# RS485_Port.net
KiCad netlist of a schematic drawn in Altium Designer
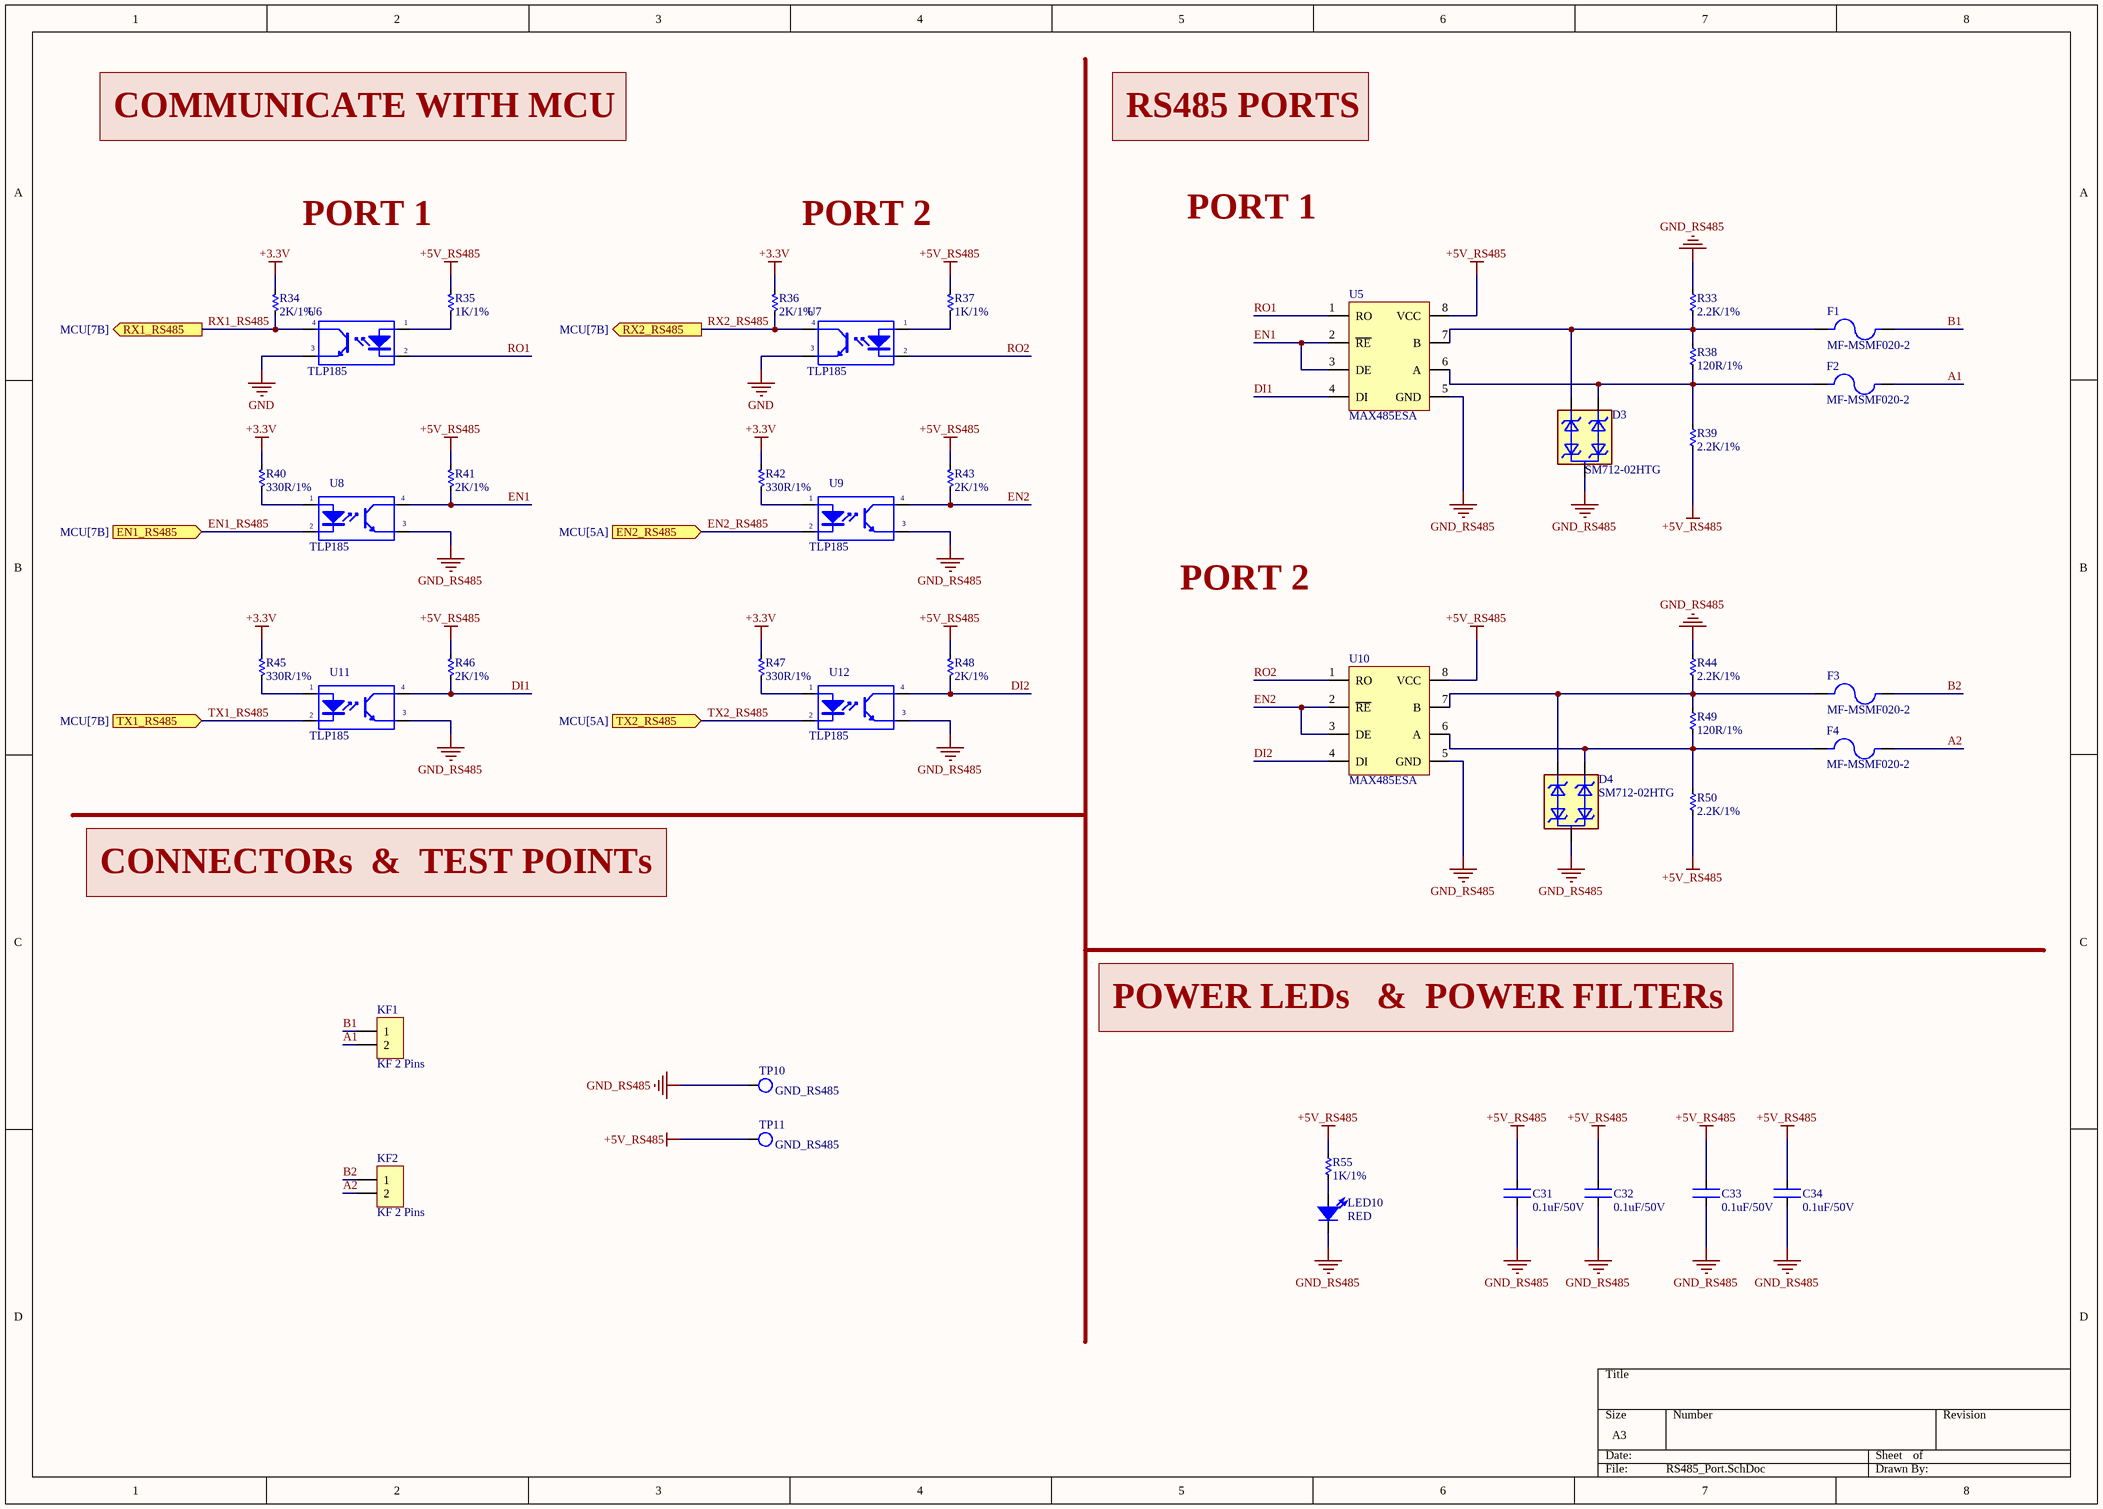
[diagram p0: RS485_Port.SchDoc]

(export (version "E")
  (design (tool "Eeschema 10.0.6"))
  (components
    (comp (ref "C31")
      (value "0.1uF/50V")
      (footprint "CAP - 0603")
      (description "CAPACITOR SMD - KEMET")
      (libsource (lib "NewLibrary") (part "CAPACITOR"))
    )
    (comp (ref "C32")
      (value "0.1uF/50V")
      (footprint "CAP - 0603")
      (description "CAPACITOR SMD - KEMET")
      (libsource (lib "NewLibrary") (part "CAPACITOR"))
    )
    (comp (ref "C33")
      (value "0.1uF/50V")
      (footprint "CAP - 0603")
      (description "CAPACITOR SMD - KEMET")
      (libsource (lib "NewLibrary") (part "CAPACITOR"))
    )
    (comp (ref "C34")
      (value "0.1uF/50V")
      (footprint "CAP - 0603")
      (description "CAPACITOR SMD - KEMET")
      (libsource (lib "NewLibrary") (part "CAPACITOR"))
    )
    (comp (ref "D3")
      (value "SM712-02HTG")
      (footprint "SOT23-3")
      (libsource (lib "NewLibrary") (part "SM712-02HTG"))
    )
    (comp (ref "D4")
      (value "SM712-02HTG")
      (footprint "SOT23-3")
      (libsource (lib "NewLibrary") (part "SM712-02HTG"))
    )
    (comp (ref "F1")
      (value "MF-MSMF020-2")
      (footprint "Fuse 4.55x3.24 mm")
      (description "Fuse Resettable 30V/0.2A; Size 4.55 x 3.24mm")
      (libsource (lib "NewLibrary") (part "MF-MSMF020-2"))
    )
    (comp (ref "F2")
      (value "MF-MSMF020-2")
      (footprint "Fuse 4.55x3.24 mm")
      (description "Fuse Resettable 30V/0.2A; Size 4.55 x 3.24mm")
      (libsource (lib "NewLibrary") (part "MF-MSMF020-2"))
    )
    (comp (ref "F3")
      (value "MF-MSMF020-2")
      (footprint "Fuse 4.55x3.24 mm")
      (description "Fuse Resettable 30V/0.2A; Size 4.55 x 3.24mm")
      (libsource (lib "NewLibrary") (part "MF-MSMF020-2"))
    )
    (comp (ref "F4")
      (value "MF-MSMF020-2")
      (footprint "Fuse 4.55x3.24 mm")
      (description "Fuse Resettable 30V/0.2A; Size 4.55 x 3.24mm")
      (libsource (lib "NewLibrary") (part "MF-MSMF020-2"))
    )
    (comp (ref "KF1")
      (value "KF 2 Pins")
      (footprint "KF-5.08-2-R")
      (description "KF Terminal Block Plug-in")
      (libsource (lib "NewLibrary") (part "KF 2 Pins"))
    )
    (comp (ref "KF2")
      (value "KF 2 Pins")
      (footprint "KF-5.08-2-R")
      (description "KF Terminal Block Plug-in")
      (libsource (lib "NewLibrary") (part "KF 2 Pins"))
    )
    (comp (ref "LED10")
      (value "RED")
      (footprint "RED_LED_0603")
      (description "LED SMD")
      (libsource (lib "NewLibrary") (part "LED_SMD"))
    )
    (comp (ref "R33")
      (value "2.2K/1%")
      (footprint "RES - 0603")
      (description "Resistor SMD - YAGEO")
      (libsource (lib "NewLibrary") (part "RESISTOR"))
    )
    (comp (ref "R34")
      (value "2K/1%")
      (footprint "RES - 0603")
      (description "Resistor SMD - YAGEO")
      (libsource (lib "NewLibrary") (part "RESISTOR"))
    )
    (comp (ref "R35")
      (value "1K/1%")
      (footprint "RES - 0603")
      (description "Resistor SMD - YAGEO")
      (libsource (lib "NewLibrary") (part "RESISTOR"))
    )
    (comp (ref "R36")
      (value "2K/1%")
      (footprint "RES - 0603")
      (description "Resistor SMD - YAGEO")
      (libsource (lib "NewLibrary") (part "RESISTOR"))
    )
    (comp (ref "R37")
      (value "1K/1%")
      (footprint "RES - 0603")
      (description "Resistor SMD - YAGEO")
      (libsource (lib "NewLibrary") (part "RESISTOR"))
    )
    (comp (ref "R38")
      (value "120R/1%")
      (footprint "RES - 0603")
      (description "Resistor SMD - YAGEO")
      (libsource (lib "NewLibrary") (part "RESISTOR"))
    )
    (comp (ref "R39")
      (value "2.2K/1%")
      (footprint "RES - 0603")
      (description "Resistor SMD - YAGEO")
      (libsource (lib "NewLibrary") (part "RESISTOR"))
    )
    (comp (ref "R40")
      (value "330R/1%")
      (footprint "RES - 0603")
      (description "Resistor SMD - YAGEO")
      (libsource (lib "NewLibrary") (part "RESISTOR"))
    )
    (comp (ref "R41")
      (value "2K/1%")
      (footprint "RES - 0603")
      (description "Resistor SMD - YAGEO")
      (libsource (lib "NewLibrary") (part "RESISTOR"))
    )
    (comp (ref "R42")
      (value "330R/1%")
      (footprint "RES - 0603")
      (description "Resistor SMD - YAGEO")
      (libsource (lib "NewLibrary") (part "RESISTOR"))
    )
    (comp (ref "R43")
      (value "2K/1%")
      (footprint "RES - 0603")
      (description "Resistor SMD - YAGEO")
      (libsource (lib "NewLibrary") (part "RESISTOR"))
    )
    (comp (ref "R44")
      (value "2.2K/1%")
      (footprint "RES - 0603")
      (description "Resistor SMD - YAGEO")
      (libsource (lib "NewLibrary") (part "RESISTOR"))
    )
    (comp (ref "R45")
      (value "330R/1%")
      (footprint "RES - 0603")
      (description "Resistor SMD - YAGEO")
      (libsource (lib "NewLibrary") (part "RESISTOR"))
    )
    (comp (ref "R46")
      (value "2K/1%")
      (footprint "RES - 0603")
      (description "Resistor SMD - YAGEO")
      (libsource (lib "NewLibrary") (part "RESISTOR"))
    )
    (comp (ref "R47")
      (value "330R/1%")
      (footprint "RES - 0603")
      (description "Resistor SMD - YAGEO")
      (libsource (lib "NewLibrary") (part "RESISTOR"))
    )
    (comp (ref "R48")
      (value "2K/1%")
      (footprint "RES - 0603")
      (description "Resistor SMD - YAGEO")
      (libsource (lib "NewLibrary") (part "RESISTOR"))
    )
    (comp (ref "R49")
      (value "120R/1%")
      (footprint "RES - 0603")
      (description "Resistor SMD - YAGEO")
      (libsource (lib "NewLibrary") (part "RESISTOR"))
    )
    (comp (ref "R50")
      (value "2.2K/1%")
      (footprint "RES - 0603")
      (description "Resistor SMD - YAGEO")
      (libsource (lib "NewLibrary") (part "RESISTOR"))
    )
    (comp (ref "R55")
      (value "1K/1%")
      (footprint "RES - 0603")
      (description "Resistor SMD - YAGEO")
      (libsource (lib "NewLibrary") (part "RESISTOR"))
    )
    (comp (ref "TP10")
      (value "GND_RS485")
      (footprint "Test Point")
      (description "Test Point")
      (libsource (lib "NewLibrary") (part "TEST POINT"))
    )
    (comp (ref "TP11")
      (value "GND_RS485")
      (footprint "Test Point")
      (description "Test Point")
      (libsource (lib "NewLibrary") (part "TEST POINT"))
    )
    (comp (ref "U5")
      (value "MAX485ESA")
      (footprint "SOP_8")
      (description "1/1 Transceiver Half RS422, RS485")
      (libsource (lib "NewLibrary") (part "MAX485ESA"))
    )
    (comp (ref "U6")
      (value "TLP185")
      (footprint "SOP-4")
      (description "TLP185 Optoisolator Transistor Output 3750Vrms 1 Channel 4-SOP")
      (libsource (lib "NewLibrary") (part "TLP185"))
    )
    (comp (ref "U7")
      (value "TLP185")
      (footprint "SOP-4")
      (description "TLP185 Optoisolator Transistor Output 3750Vrms 1 Channel 4-SOP")
      (libsource (lib "NewLibrary") (part "TLP185"))
    )
    (comp (ref "U8")
      (value "TLP185")
      (footprint "SOP-4")
      (description "TLP185 Optoisolator Transistor Output 3750Vrms 1 Channel 4-SOP")
      (libsource (lib "NewLibrary") (part "TLP185"))
    )
    (comp (ref "U9")
      (value "TLP185")
      (footprint "SOP-4")
      (description "TLP185 Optoisolator Transistor Output 3750Vrms 1 Channel 4-SOP")
      (libsource (lib "NewLibrary") (part "TLP185"))
    )
    (comp (ref "U10")
      (value "MAX485ESA")
      (footprint "SOP_8")
      (description "1/1 Transceiver Half RS422, RS485")
      (libsource (lib "NewLibrary") (part "MAX485ESA"))
    )
    (comp (ref "U11")
      (value "TLP185")
      (footprint "SOP-4")
      (description "TLP185 Optoisolator Transistor Output 3750Vrms 1 Channel 4-SOP")
      (libsource (lib "NewLibrary") (part "TLP185"))
    )
    (comp (ref "U12")
      (value "TLP185")
      (footprint "SOP-4")
      (description "TLP185 Optoisolator Transistor Output 3750Vrms 1 Channel 4-SOP")
      (libsource (lib "NewLibrary") (part "TLP185"))
    )
  )
  (nets
    (net (code "1") (name "+3.3V") (class "Default")
      (node (ref "R34") (pin "2") (pinfunction "2_2") (pintype "passive"))
      (node (ref "R36") (pin "2") (pinfunction "2_2") (pintype "passive"))
      (node (ref "R40") (pin "2") (pinfunction "2_2") (pintype "passive"))
      (node (ref "R42") (pin "2") (pinfunction "2_2") (pintype "passive"))
      (node (ref "R45") (pin "2") (pinfunction "2_2") (pintype "passive"))
      (node (ref "R47") (pin "2") (pinfunction "2_2") (pintype "passive"))
    )
    (net (code "2") (name "+5V_RS485") (class "Default")
      (node (ref "C31") (pin "1") (pinfunction "1_1") (pintype "passive"))
      (node (ref "C32") (pin "1") (pinfunction "1_1") (pintype "passive"))
      (node (ref "C33") (pin "1") (pinfunction "1_1") (pintype "passive"))
      (node (ref "C34") (pin "1") (pinfunction "1_1") (pintype "passive"))
      (node (ref "R35") (pin "2") (pinfunction "2_2") (pintype "passive"))
      (node (ref "R37") (pin "2") (pinfunction "2_2") (pintype "passive"))
      (node (ref "R39") (pin "1") (pinfunction "1_1") (pintype "passive"))
      (node (ref "R41") (pin "2") (pinfunction "2_2") (pintype "passive"))
      (node (ref "R43") (pin "2") (pinfunction "2_2") (pintype "passive"))
      (node (ref "R46") (pin "2") (pinfunction "2_2") (pintype "passive"))
      (node (ref "R48") (pin "2") (pinfunction "2_2") (pintype "passive"))
      (node (ref "R50") (pin "1") (pinfunction "1_1") (pintype "passive"))
      (node (ref "R55") (pin "1") (pinfunction "1_1") (pintype "passive"))
      (node (ref "TP11") (pin "1") (pinfunction "1_1") (pintype "passive"))
      (node (ref "U10") (pin "8") (pinfunction "VCC_8") (pintype "passive"))
      (node (ref "U5") (pin "8") (pinfunction "VCC_8") (pintype "passive"))
    )
    (net (code "3") (name "/A1") (class "Default")
      (node (ref "F2") (pin "2") (pinfunction "2_2") (pintype "passive"))
      (node (ref "KF1") (pin "2") (pinfunction "2_2") (pintype "passive"))
    )
    (net (code "4") (name "/A2") (class "Default")
      (node (ref "F4") (pin "2") (pinfunction "2_2") (pintype "passive"))
      (node (ref "KF2") (pin "2") (pinfunction "2_2") (pintype "passive"))
    )
    (net (code "5") (name "/B1") (class "Default")
      (node (ref "F1") (pin "2") (pinfunction "2_2") (pintype "passive"))
      (node (ref "KF1") (pin "1") (pinfunction "1_1") (pintype "passive"))
    )
    (net (code "6") (name "/B2") (class "Default")
      (node (ref "F3") (pin "2") (pinfunction "2_2") (pintype "passive"))
      (node (ref "KF2") (pin "1") (pinfunction "1_1") (pintype "passive"))
    )
    (net (code "7") (name "/DI1") (class "Default")
      (node (ref "R46") (pin "1") (pinfunction "1_1") (pintype "passive"))
      (node (ref "U11") (pin "4") (pinfunction "C_4") (pintype "passive"))
      (node (ref "U5") (pin "4") (pinfunction "DI_4") (pintype "passive"))
    )
    (net (code "8") (name "/DI2") (class "Default")
      (node (ref "R48") (pin "1") (pinfunction "1_1") (pintype "passive"))
      (node (ref "U10") (pin "4") (pinfunction "DI_4") (pintype "passive"))
      (node (ref "U12") (pin "4") (pinfunction "C_4") (pintype "passive"))
    )
    (net (code "9") (name "/EN1") (class "Default")
      (node (ref "R41") (pin "1") (pinfunction "1_1") (pintype "passive"))
      (node (ref "U5") (pin "2") (pinfunction "~{RE}_2") (pintype "passive"))
      (node (ref "U5") (pin "3") (pinfunction "DE_3") (pintype "passive"))
      (node (ref "U8") (pin "4") (pinfunction "C_4") (pintype "passive"))
    )
    (net (code "10") (name "/EN1_RS485") (class "Default")
      (node (ref "U8") (pin "2") (pinfunction "K_2") (pintype "passive"))
    )
    (net (code "11") (name "/EN2") (class "Default")
      (node (ref "R43") (pin "1") (pinfunction "1_1") (pintype "passive"))
      (node (ref "U10") (pin "2") (pinfunction "~{RE}_2") (pintype "passive"))
      (node (ref "U10") (pin "3") (pinfunction "DE_3") (pintype "passive"))
      (node (ref "U9") (pin "4") (pinfunction "C_4") (pintype "passive"))
    )
    (net (code "12") (name "/EN2_RS485") (class "Default")
      (node (ref "U9") (pin "2") (pinfunction "K_2") (pintype "passive"))
    )
    (net (code "13") (name "/RO1") (class "Default")
      (node (ref "U5") (pin "1") (pinfunction "RO_1") (pintype "passive"))
      (node (ref "U6") (pin "2") (pinfunction "K_2") (pintype "passive"))
    )
    (net (code "14") (name "/RO2") (class "Default")
      (node (ref "U10") (pin "1") (pinfunction "RO_1") (pintype "passive"))
      (node (ref "U7") (pin "2") (pinfunction "K_2") (pintype "passive"))
    )
    (net (code "15") (name "/RX1_RS485") (class "Default")
      (node (ref "R34") (pin "1") (pinfunction "1_1") (pintype "passive"))
      (node (ref "U6") (pin "4") (pinfunction "C_4") (pintype "passive"))
    )
    (net (code "16") (name "/RX2_RS485") (class "Default")
      (node (ref "R36") (pin "1") (pinfunction "1_1") (pintype "passive"))
      (node (ref "U7") (pin "4") (pinfunction "C_4") (pintype "passive"))
    )
    (net (code "17") (name "/TX1_RS485") (class "Default")
      (node (ref "U11") (pin "2") (pinfunction "K_2") (pintype "passive"))
    )
    (net (code "18") (name "/TX2_RS485") (class "Default")
      (node (ref "U12") (pin "2") (pinfunction "K_2") (pintype "passive"))
    )
    (net (code "19") (name "GND") (class "Default")
      (node (ref "U6") (pin "3") (pinfunction "E_3") (pintype "passive"))
      (node (ref "U7") (pin "3") (pinfunction "E_3") (pintype "passive"))
    )
    (net (code "20") (name "GND_RS485") (class "Default")
      (node (ref "C31") (pin "2") (pinfunction "2_2") (pintype "passive"))
      (node (ref "C32") (pin "2") (pinfunction "2_2") (pintype "passive"))
      (node (ref "C33") (pin "2") (pinfunction "2_2") (pintype "passive"))
      (node (ref "C34") (pin "2") (pinfunction "2_2") (pintype "passive"))
      (node (ref "D3") (pin "3") (pinfunction "3_3") (pintype "passive"))
      (node (ref "D4") (pin "3") (pinfunction "3_3") (pintype "passive"))
      (node (ref "LED10") (pin "2") (pinfunction "2_2") (pintype "passive"))
      (node (ref "R33") (pin "2") (pinfunction "2_2") (pintype "passive"))
      (node (ref "R44") (pin "2") (pinfunction "2_2") (pintype "passive"))
      (node (ref "TP10") (pin "1") (pinfunction "1_1") (pintype "passive"))
      (node (ref "U10") (pin "5") (pinfunction "GND_5") (pintype "passive"))
      (node (ref "U11") (pin "3") (pinfunction "E_3") (pintype "passive"))
      (node (ref "U12") (pin "3") (pinfunction "E_3") (pintype "passive"))
      (node (ref "U5") (pin "5") (pinfunction "GND_5") (pintype "passive"))
      (node (ref "U8") (pin "3") (pinfunction "E_3") (pintype "passive"))
      (node (ref "U9") (pin "3") (pinfunction "E_3") (pintype "passive"))
    )
    (net (code "21") (name "Net-(LED10-Pad1)") (class "Default")
      (node (ref "LED10") (pin "1") (pinfunction "1_1") (pintype "passive"))
      (node (ref "R55") (pin "2") (pinfunction "2_2") (pintype "passive"))
    )
    (net (code "22") (name "Net-(U5-A)") (class "Default")
      (node (ref "D3") (pin "1") (pinfunction "1_1") (pintype "passive"))
      (node (ref "F2") (pin "1") (pinfunction "1_1") (pintype "passive"))
      (node (ref "R38") (pin "1") (pinfunction "1_1") (pintype "passive"))
      (node (ref "R39") (pin "2") (pinfunction "2_2") (pintype "passive"))
      (node (ref "U5") (pin "6") (pinfunction "A_6") (pintype "passive"))
    )
    (net (code "23") (name "Net-(U5-B)") (class "Default")
      (node (ref "D3") (pin "2") (pinfunction "2_2") (pintype "passive"))
      (node (ref "F1") (pin "1") (pinfunction "1_1") (pintype "passive"))
      (node (ref "R33") (pin "1") (pinfunction "1_1") (pintype "passive"))
      (node (ref "R38") (pin "2") (pinfunction "2_2") (pintype "passive"))
      (node (ref "U5") (pin "7") (pinfunction "B_7") (pintype "passive"))
    )
    (net (code "24") (name "Net-(U6-A)") (class "Default")
      (node (ref "R35") (pin "1") (pinfunction "1_1") (pintype "passive"))
      (node (ref "U6") (pin "1") (pinfunction "A_1") (pintype "passive"))
    )
    (net (code "25") (name "Net-(U7-A)") (class "Default")
      (node (ref "R37") (pin "1") (pinfunction "1_1") (pintype "passive"))
      (node (ref "U7") (pin "1") (pinfunction "A_1") (pintype "passive"))
    )
    (net (code "26") (name "Net-(U8-A)") (class "Default")
      (node (ref "R40") (pin "1") (pinfunction "1_1") (pintype "passive"))
      (node (ref "U8") (pin "1") (pinfunction "A_1") (pintype "passive"))
    )
    (net (code "27") (name "Net-(U9-A)") (class "Default")
      (node (ref "R42") (pin "1") (pinfunction "1_1") (pintype "passive"))
      (node (ref "U9") (pin "1") (pinfunction "A_1") (pintype "passive"))
    )
    (net (code "28") (name "Net-(U10-A)") (class "Default")
      (node (ref "D4") (pin "1") (pinfunction "1_1") (pintype "passive"))
      (node (ref "F4") (pin "1") (pinfunction "1_1") (pintype "passive"))
      (node (ref "R49") (pin "1") (pinfunction "1_1") (pintype "passive"))
      (node (ref "R50") (pin "2") (pinfunction "2_2") (pintype "passive"))
      (node (ref "U10") (pin "6") (pinfunction "A_6") (pintype "passive"))
    )
    (net (code "29") (name "Net-(U10-B)") (class "Default")
      (node (ref "D4") (pin "2") (pinfunction "2_2") (pintype "passive"))
      (node (ref "F3") (pin "1") (pinfunction "1_1") (pintype "passive"))
      (node (ref "R44") (pin "1") (pinfunction "1_1") (pintype "passive"))
      (node (ref "R49") (pin "2") (pinfunction "2_2") (pintype "passive"))
      (node (ref "U10") (pin "7") (pinfunction "B_7") (pintype "passive"))
    )
    (net (code "30") (name "Net-(U11-A)") (class "Default")
      (node (ref "R45") (pin "1") (pinfunction "1_1") (pintype "passive"))
      (node (ref "U11") (pin "1") (pinfunction "A_1") (pintype "passive"))
    )
    (net (code "31") (name "Net-(U12-A)") (class "Default")
      (node (ref "R47") (pin "1") (pinfunction "1_1") (pintype "passive"))
      (node (ref "U12") (pin "1") (pinfunction "A_1") (pintype "passive"))
    )
  )
)
